# MPVZ5010_pressureButton.net
KiCad netlist of a schematic drawn in EAGLE
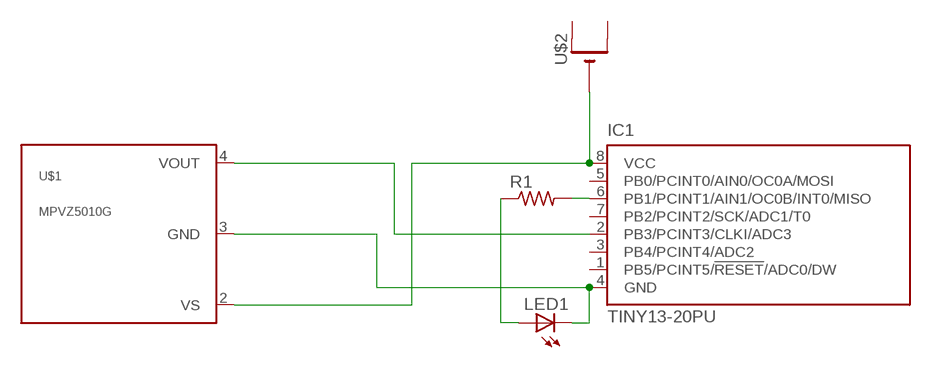
[diagram p0: schematic, sheet 1]

(export (version "E")
  (design (tool "Eeschema 10.0.6"))
  (components
    (comp (ref "IC1")
      (value "TINY13-20PU")
      (footprint "eagle-import:DIL08")
      (fields (field (name "MPN") "ATTINY13-20PU"))
      (libsource (lib "eagle-import") (part "TINY13PU-20"))
    )
    (comp (ref "LED1")
      (value "LED3MM")
      (footprint "eagle-import:LED3MM")
      (libsource (lib "eagle-import") (part "LED3MM"))
    )
    (comp (ref "R1")
      (value "R-US_R0805")
      (footprint "eagle-import:R0805")
      (libsource (lib "eagle-import") (part "R-US_R0805"))
    )
    (comp (ref "U$1")
      (value "MPVZ5010G")
      (footprint "eagle-import:PVZ5010GW6U")
      (libsource (lib "eagle-import") (part "MPVZ5010G"))
    )
    (comp (ref "U$2")
      (value "CR1220THM")
      (footprint "eagle-import:CR1220-THM")
      (libsource (lib "eagle-import") (part "CR1220THM"))
    )
  )
  (nets
    (net (code "1") (name "Net-(IC1-GND)") (class "Default")
      (node (ref "IC1") (pin "4") (pinfunction "GND_4") (pintype "power_in"))
      (node (ref "LED1") (pin "K") (pinfunction "C_K") (pintype "passive"))
      (node (ref "U$1") (pin "3") (pinfunction "GND_3") (pintype "power_in"))
    )
    (net (code "2") (name "Net-(IC1-PB1{slash}PCINT1{slash}AIN1{slash}OC0B{slash}INT0{slash}MISO)") (class "Default")
      (node (ref "IC1") (pin "6") (pinfunction "PB1/PCINT1/AIN1/OC0B/INT0/MISO_6") (pintype "bidirectional"))
      (node (ref "R1") (pin "2") (pinfunction "2_2") (pintype "passive"))
    )
    (net (code "3") (name "Net-(IC1-PB3{slash}PCINT3{slash}CLKI{slash}ADC3)") (class "Default")
      (node (ref "IC1") (pin "2") (pinfunction "PB3/PCINT3/CLKI/ADC3_2") (pintype "bidirectional"))
      (node (ref "U$1") (pin "4") (pinfunction "VOUT_4") (pintype "output"))
    )
    (net (code "4") (name "Net-(IC1-VCC)") (class "Default")
      (node (ref "IC1") (pin "8") (pinfunction "VCC_8") (pintype "power_in"))
      (node (ref "U$1") (pin "2") (pinfunction "VS_2") (pintype "power_in"))
      (node (ref "U$2") (pin "-") (pinfunction "-_-") (pintype "passive"))
    )
    (net (code "5") (name "Net-(LED1-PadA)") (class "Default")
      (node (ref "LED1") (pin "A") (pinfunction "A_A") (pintype "passive"))
      (node (ref "R1") (pin "1") (pinfunction "1_1") (pintype "passive"))
    )
    (net (code "6") (name "unconnected-(IC1-PB0{slash}PCINT0{slash}AIN0{slash}OC0A{slash}MOSI-Pad5)") (class "Default")
      (node (ref "IC1") (pin "5") (pinfunction "PB0/PCINT0/AIN0/OC0A/MOSI_5") (pintype "bidirectional"))
    )
    (net (code "7") (name "unconnected-(IC1-PB2{slash}PCINT2{slash}SCK{slash}ADC1{slash}T0-Pad7)") (class "Default")
      (node (ref "IC1") (pin "7") (pinfunction "PB2/PCINT2/SCK/ADC1/T0_7") (pintype "bidirectional"))
    )
    (net (code "8") (name "unconnected-(IC1-PB4{slash}PCINT4{slash}ADC2-Pad3)") (class "Default")
      (node (ref "IC1") (pin "3") (pinfunction "PB4/PCINT4/ADC2_3") (pintype "bidirectional"))
    )
    (net (code "9") (name "unconnected-(IC1-PB5{slash}PCINT5{slash}~{RESET}{slash}ADC0{slash}DW-Pad1)") (class "Default")
      (node (ref "IC1") (pin "1") (pinfunction "PB5/PCINT5/~{RESET}/ADC0/DW_1") (pintype "bidirectional"))
    )
    (net (code "10") (name "unconnected-(U$2-+-Pad+1)") (class "Default")
      (node (ref "U$2") (pin "+1") (pinfunction "+_+1") (pintype "passive"))
    )
    (net (code "11") (name "unconnected-(U$2-+1-Pad+2)") (class "Default")
      (node (ref "U$2") (pin "+2") (pinfunction "+1_+2") (pintype "passive"))
    )
  )
)
